# DVR8412.net
KiCad netlist of a schematic drawn in Altium Designer
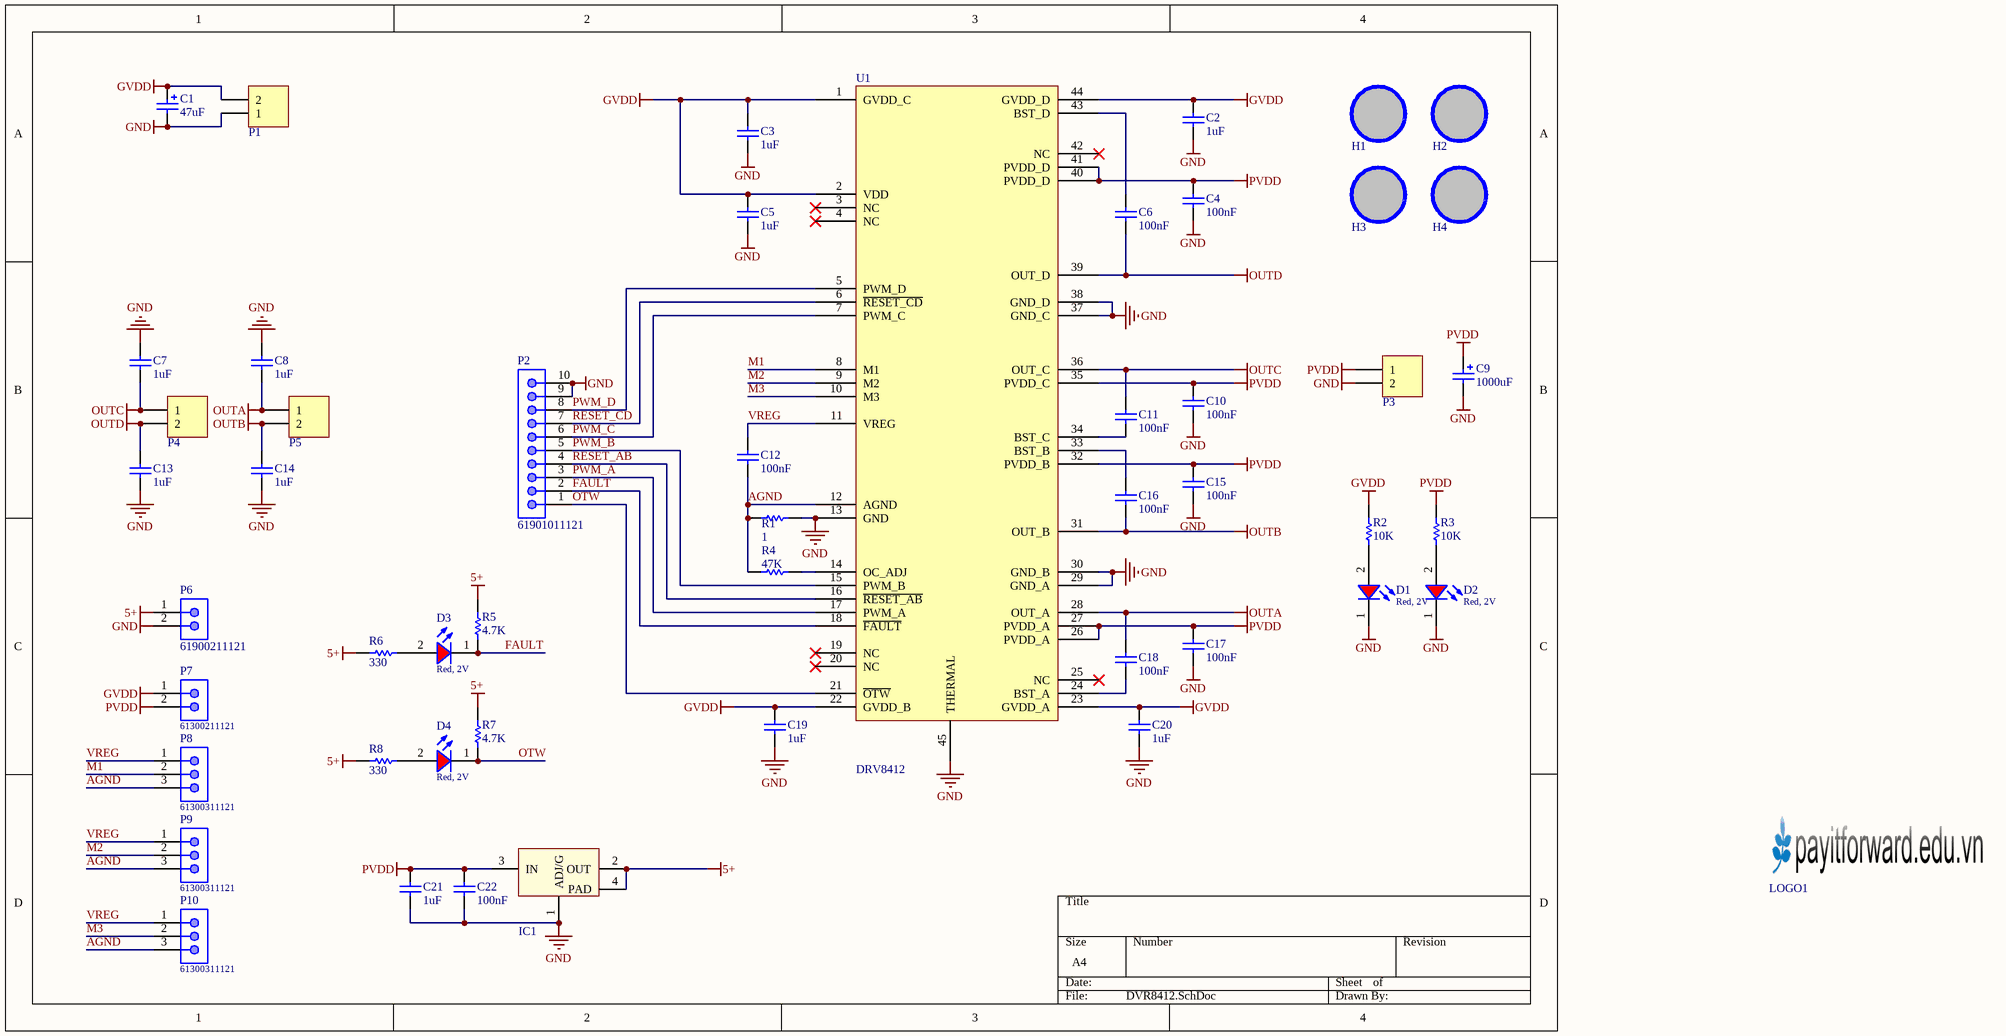
[diagram p0: DVR8412.SchDoc]

(export (version "E")
  (design (tool "Eeschema 10.0.6"))
  (components
    (comp (ref "C1")
      (value "47uF")
      (footprint "CAP ALU SIZE D")
      (description "Polarized Capacitor (Radial)")
      (fields (field (name "Comment") "Cap Pol SMD"))
      (libsource (lib "PIF_Library") (part "Cap Pol SMD"))
    )
    (comp (ref "C2")
      (value "1uF")
      (footprint "CAP-SM-0603")
      (description "Capacitor")
      (fields (field (name "Comment") "Cap Non-Pol SMD"))
      (libsource (lib "PIF_Library") (part "Cap Non-Pol SMD"))
    )
    (comp (ref "C3")
      (value "1uF")
      (footprint "CAP-SM-0603")
      (description "Capacitor")
      (fields (field (name "Comment") "Cap Non-Pol SMD"))
      (libsource (lib "PIF_Library") (part "Cap Non-Pol SMD"))
    )
    (comp (ref "C4")
      (value "100nF")
      (footprint "CAP-SM-0603")
      (description "Capacitor")
      (fields (field (name "Comment") "Cap Non-Pol SMD"))
      (libsource (lib "PIF_Library") (part "Cap Non-Pol SMD"))
    )
    (comp (ref "C5")
      (value "1uF")
      (footprint "CAP-SM-0603")
      (description "Capacitor")
      (fields (field (name "Comment") "Cap Non-Pol SMD"))
      (libsource (lib "PIF_Library") (part "Cap Non-Pol SMD"))
    )
    (comp (ref "C6")
      (value "100nF")
      (footprint "CAP-SM-0603")
      (description "Capacitor")
      (fields (field (name "Comment") "Cap Non-Pol SMD"))
      (libsource (lib "PIF_Library") (part "Cap Non-Pol SMD"))
    )
    (comp (ref "C7")
      (value "1uF")
      (footprint "CAP-SM-0805")
      (description "Capacitor")
      (fields (field (name "Comment") "Cap Non-Pol SMD"))
      (libsource (lib "PIF_Library") (part "Cap Non-Pol SMD"))
    )
    (comp (ref "C8")
      (value "1uF")
      (footprint "CAP-SM-0805")
      (description "Capacitor")
      (fields (field (name "Comment") "Cap Non-Pol SMD"))
      (libsource (lib "PIF_Library") (part "Cap Non-Pol SMD"))
    )
    (comp (ref "C9")
      (value "1000uF")
      (footprint "CP2/5")
      (description "Polarized Capacitor (Radial)")
      (fields (field (name "Comment") "Cap Pol"))
      (libsource (lib "PIF_Library") (part "Cap Pol"))
    )
    (comp (ref "C10")
      (value "100nF")
      (footprint "CAP-SM-0603")
      (description "Capacitor")
      (fields (field (name "Comment") "Cap Non-Pol SMD"))
      (libsource (lib "PIF_Library") (part "Cap Non-Pol SMD"))
    )
    (comp (ref "C11")
      (value "100nF")
      (footprint "CAP-SM-0603")
      (description "Capacitor")
      (fields (field (name "Comment") "Cap Non-Pol SMD"))
      (libsource (lib "PIF_Library") (part "Cap Non-Pol SMD"))
    )
    (comp (ref "C12")
      (value "100nF")
      (footprint "CAP-SM-0603")
      (description "Capacitor")
      (fields (field (name "Comment") "Cap Non-Pol SMD"))
      (libsource (lib "PIF_Library") (part "Cap Non-Pol SMD"))
    )
    (comp (ref "C13")
      (value "1uF")
      (footprint "CAP-SM-0805")
      (description "Capacitor")
      (fields (field (name "Comment") "Cap Non-Pol SMD"))
      (libsource (lib "PIF_Library") (part "Cap Non-Pol SMD"))
    )
    (comp (ref "C14")
      (value "1uF")
      (footprint "CAP-SM-0805")
      (description "Capacitor")
      (fields (field (name "Comment") "Cap Non-Pol SMD"))
      (libsource (lib "PIF_Library") (part "Cap Non-Pol SMD"))
    )
    (comp (ref "C15")
      (value "100nF")
      (footprint "CAP-SM-0603")
      (description "Capacitor")
      (fields (field (name "Comment") "Cap Non-Pol SMD"))
      (libsource (lib "PIF_Library") (part "Cap Non-Pol SMD"))
    )
    (comp (ref "C16")
      (value "100nF")
      (footprint "CAP-SM-0603")
      (description "Capacitor")
      (fields (field (name "Comment") "Cap Non-Pol SMD"))
      (libsource (lib "PIF_Library") (part "Cap Non-Pol SMD"))
    )
    (comp (ref "C17")
      (value "100nF")
      (footprint "CAP-SM-0603")
      (description "Capacitor")
      (fields (field (name "Comment") "Cap Non-Pol SMD"))
      (libsource (lib "PIF_Library") (part "Cap Non-Pol SMD"))
    )
    (comp (ref "C18")
      (value "100nF")
      (footprint "CAP-SM-0603")
      (description "Capacitor")
      (fields (field (name "Comment") "Cap Non-Pol SMD"))
      (libsource (lib "PIF_Library") (part "Cap Non-Pol SMD"))
    )
    (comp (ref "C19")
      (value "1uF")
      (footprint "CAP-SM-0603")
      (description "Capacitor")
      (fields (field (name "Comment") "Cap Non-Pol SMD"))
      (libsource (lib "PIF_Library") (part "Cap Non-Pol SMD"))
    )
    (comp (ref "C20")
      (value "1uF")
      (footprint "CAP-SM-0603")
      (description "Capacitor")
      (fields (field (name "Comment") "Cap Non-Pol SMD"))
      (libsource (lib "PIF_Library") (part "Cap Non-Pol SMD"))
    )
    (comp (ref "C21")
      (value "1uF")
      (footprint "CAP-SM-0603")
      (description "Capacitor")
      (fields (field (name "Comment") "Cap Non-Pol SMD"))
      (libsource (lib "PIF_Library") (part "Cap Non-Pol SMD"))
    )
    (comp (ref "C22")
      (value "100nF")
      (footprint "CAP-SM-0603")
      (description "Capacitor")
      (fields (field (name "Comment") "Cap Non-Pol SMD"))
      (libsource (lib "PIF_Library") (part "Cap Non-Pol SMD"))
    )
    (comp (ref "D1")
      (value "Red, 2V")
      (footprint "WL-SMCW_0603_H=0.7mm")
      (description "WL-SMCW SMT Mono-color Chip LED Waterclear, size 0603, Red, 2V, 140deg")
      (fields (field (name "PART NUMBER") "150060RS75000") (field (name "PUBLISHER") "Wurth Elektronik"))
      (libsource (lib "Altium_WL-SMCW (rev20a)") (part "150060RS75000"))
    )
    (comp (ref "D2")
      (value "Red, 2V")
      (footprint "WL-SMCW_0603_H=0.7mm")
      (description "WL-SMCW SMT Mono-color Chip LED Waterclear, size 0603, Red, 2V, 140deg")
      (fields (field (name "PART NUMBER") "150060RS75000") (field (name "PUBLISHER") "Wurth Elektronik"))
      (libsource (lib "Altium_WL-SMCW (rev20a)") (part "150060RS75000"))
    )
    (comp (ref "D3")
      (value "Red, 2V")
      (footprint "WL-SMCW_0603_H=0.7mm")
      (description "WL-SMCW SMT Mono-color Chip LED Waterclear, size 0603, Red, 2V, 140deg")
      (fields (field (name "PART NUMBER") "150060RS75000") (field (name "PUBLISHER") "Wurth Elektronik"))
      (libsource (lib "Altium_WL-SMCW (rev20a)") (part "150060RS75000"))
    )
    (comp (ref "D4")
      (value "Red, 2V")
      (footprint "WL-SMCW_0603_H=0.7mm")
      (description "WL-SMCW SMT Mono-color Chip LED Waterclear, size 0603, Red, 2V, 140deg")
      (fields (field (name "PART NUMBER") "150060RS75000") (field (name "PUBLISHER") "Wurth Elektronik"))
      (libsource (lib "Altium_WL-SMCW (rev20a)") (part "150060RS75000"))
    )
    (comp (ref "H1")
      (value "Hole")
      (footprint "LO KHOAN 3MM")
      (description "Hole 3mm")
      (libsource (lib "PIF_Library") (part "Hole"))
    )
    (comp (ref "H2")
      (value "Hole")
      (footprint "LO KHOAN 3MM")
      (description "Hole 3mm")
      (libsource (lib "PIF_Library") (part "Hole"))
    )
    (comp (ref "H3")
      (value "Hole")
      (footprint "LO KHOAN 3MM")
      (description "Hole 3mm")
      (libsource (lib "PIF_Library") (part "Hole"))
    )
    (comp (ref "H4")
      (value "Hole")
      (footprint "LO KHOAN 3MM")
      (description "Hole 3mm")
      (libsource (lib "PIF_Library") (part "Hole"))
    )
    (comp (ref "IC1")
      (value "LM1117")
      (footprint "SOT223-4N")
      (description "Available in 1.8V, 2.5V, 2.85V, 3.3V, 5V, and  Adjustable Versions")
      (libsource (lib "PIF_Library") (part "LM1117"))
    )
    (comp (ref "LOGO1")
      (value "LOGO PIF")
      (footprint "PIF LOGO SMALL TOP")
      (libsource (lib "PIF_Library") (part "LOGO PIF"))
    )
    (comp (ref "P1")
      (value "Domino 2")
      (footprint "DOMINO 2- 5mm")
      (description "Domino, 2-Pin")
      (fields (field (name "PUBLISHER") "Altium Limited"))
      (libsource (lib "") (part "Domino 2_1"))
    )
    (comp (ref "P2")
      (value "61901011121")
      (footprint "61901011121")
      (description "WR-WTB THT Male Vertical Locking Header, pitch 2.54mm, 10p")
      (fields (field (name "PUBLISHER") "Wurth Elektronik"))
      (libsource (lib "653008114822_Altium_WR-WTB_rev20a") (part "61901011121"))
    )
    (comp (ref "P3")
      (value "Domino 2")
      (footprint "DOMINO 2- 5mm")
      (description "Domino, 2-Pin")
      (fields (field (name "PUBLISHER") "Altium Limited"))
      (libsource (lib "PIF_Library") (part "Domino 2"))
    )
    (comp (ref "P4")
      (value "Domino 2")
      (footprint "DOMINO 2- 5mm")
      (description "Domino, 2-Pin")
      (fields (field (name "PUBLISHER") "Altium Limited"))
      (libsource (lib "PIF_Library") (part "Domino 2"))
    )
    (comp (ref "P5")
      (value "Domino 2")
      (footprint "DOMINO 2- 5mm")
      (description "Domino, 2-Pin")
      (fields (field (name "PUBLISHER") "Altium Limited"))
      (libsource (lib "PIF_Library") (part "Domino 2"))
    )
    (comp (ref "P6")
      (value "61900211121")
      (footprint "61900211121")
      (description "WR-WTB THT Male Vertical Locking Header, pitch 2.54mm, 2p")
      (fields (field (name "PUBLISHER") "Wurth Elektronik"))
      (libsource (lib "653008114822_Altium_WR-WTB_rev20a") (part "61900211121"))
    )
    (comp (ref "P7")
      (value "61300211121")
      (footprint "61300211121")
      (description "WR-PHD Pin Header, THT, pitch 2.54mm, Single Row, Vertical, 2p")
      (fields (field (name "MANUFACTURER") "Wurth Elektronik"))
      (libsource (lib "Altium_WR-PHD (rev20a)") (part "61300211121"))
    )
    (comp (ref "P8")
      (value "61300311121")
      (footprint "61300311121")
      (description "WR-PHD Pin Header, THT, pitch 2.54mm, Single Row, Vertical, 3p")
      (fields (field (name "MANUFACTURER") "Wurth Elektronik"))
      (libsource (lib "Altium_WR-PHD (rev20a)") (part "61300311121"))
    )
    (comp (ref "P9")
      (value "61300311121")
      (footprint "61300311121")
      (description "WR-PHD Pin Header, THT, pitch 2.54mm, Single Row, Vertical, 3p")
      (fields (field (name "MANUFACTURER") "Wurth Elektronik"))
      (libsource (lib "Altium_WR-PHD (rev20a)") (part "61300311121"))
    )
    (comp (ref "P10")
      (value "61300311121")
      (footprint "61300311121")
      (description "WR-PHD Pin Header, THT, pitch 2.54mm, Single Row, Vertical, 3p")
      (fields (field (name "MANUFACTURER") "Wurth Elektronik"))
      (libsource (lib "Altium_WR-PHD (rev20a)") (part "61300311121"))
    )
    (comp (ref "R1")
      (value "1")
      (footprint "RES-SM-0603")
      (description "Resistor")
      (fields (field (name "Comment") "RESISTOR SMD"))
      (libsource (lib "PIF_Library") (part "RESISTOR SMD"))
    )
    (comp (ref "R2")
      (value "10K")
      (footprint "RES-SM-0603")
      (description "Resistor")
      (fields (field (name "Comment") "RESISTOR SMD"))
      (libsource (lib "PIF_Library") (part "RESISTOR SMD"))
    )
    (comp (ref "R3")
      (value "10K")
      (footprint "RES-SM-0603")
      (description "Resistor")
      (fields (field (name "Comment") "RESISTOR SMD"))
      (libsource (lib "PIF_Library") (part "RESISTOR SMD"))
    )
    (comp (ref "R4")
      (value "47K")
      (footprint "RES-SM-0603")
      (description "Resistor")
      (fields (field (name "Comment") "RESISTOR SMD"))
      (libsource (lib "PIF_Library") (part "RESISTOR SMD"))
    )
    (comp (ref "R5")
      (value "4.7K")
      (footprint "RES-SM-0603")
      (description "Resistor")
      (fields (field (name "Comment") "RESISTOR SMD"))
      (libsource (lib "PIF_Library") (part "RESISTOR SMD"))
    )
    (comp (ref "R6")
      (value "330")
      (footprint "RES-SM-0603")
      (description "Resistor")
      (fields (field (name "Comment") "RESISTOR SMD"))
      (libsource (lib "PIF_Library") (part "RESISTOR SMD"))
    )
    (comp (ref "R7")
      (value "4.7K")
      (footprint "RES-SM-0603")
      (description "Resistor")
      (fields (field (name "Comment") "RESISTOR SMD"))
      (libsource (lib "PIF_Library") (part "RESISTOR SMD"))
    )
    (comp (ref "R8")
      (value "330")
      (footprint "RES-SM-0603")
      (description "Resistor")
      (fields (field (name "Comment") "RESISTOR SMD"))
      (libsource (lib "PIF_Library") (part "RESISTOR SMD"))
    )
    (comp (ref "U1")
      (value "DRV8412")
      (footprint "TSOP64P810X150_HS-45N")
      (fields (field (name "MANUFACTURER") "Texas Instruments"))
      (libsource (lib "MiclsLib") (part "DRV8412"))
    )
  )
  (nets
    (net (code "1") (name "/AGND") (class "Default")
      (node (ref "C12") (pin "1") (pinfunction "1_1") (pintype "passive"))
      (node (ref "P10") (pin "3") (pinfunction "3_3") (pintype "passive"))
      (node (ref "P8") (pin "3") (pinfunction "3_3") (pintype "passive"))
      (node (ref "P9") (pin "3") (pinfunction "3_3") (pintype "passive"))
      (node (ref "R1") (pin "1") (pinfunction "1_1") (pintype "passive"))
      (node (ref "R4") (pin "1") (pinfunction "1_1") (pintype "passive"))
      (node (ref "U1") (pin "12") (pinfunction "AGND_12") (pintype "passive"))
    )
    (net (code "2") (name "/FAULT") (class "Default")
      (node (ref "D3") (pin "1") (pinfunction "K_1") (pintype "passive"))
      (node (ref "P2") (pin "2") (pinfunction "2_2") (pintype "passive"))
      (node (ref "R5") (pin "1") (pinfunction "1_1") (pintype "passive"))
      (node (ref "U1") (pin "18") (pinfunction "~{FAULT}_18") (pintype "passive"))
    )
    (net (code "3") (name "/M1") (class "Default")
      (node (ref "P8") (pin "2") (pinfunction "2_2") (pintype "passive"))
      (node (ref "U1") (pin "8") (pinfunction "M1_8") (pintype "passive"))
    )
    (net (code "4") (name "/M2") (class "Default")
      (node (ref "P9") (pin "2") (pinfunction "2_2") (pintype "passive"))
      (node (ref "U1") (pin "9") (pinfunction "M2_9") (pintype "passive"))
    )
    (net (code "5") (name "/M3") (class "Default")
      (node (ref "P10") (pin "2") (pinfunction "2_2") (pintype "passive"))
      (node (ref "U1") (pin "10") (pinfunction "M3_10") (pintype "passive"))
    )
    (net (code "6") (name "/OTW") (class "Default")
      (node (ref "D4") (pin "1") (pinfunction "K_1") (pintype "passive"))
      (node (ref "P2") (pin "1") (pinfunction "1_1") (pintype "passive"))
      (node (ref "R7") (pin "1") (pinfunction "1_1") (pintype "passive"))
      (node (ref "U1") (pin "21") (pinfunction "~{OTW}_21") (pintype "passive"))
    )
    (net (code "7") (name "/PWM_A") (class "Default")
      (node (ref "P2") (pin "3") (pinfunction "3_3") (pintype "passive"))
      (node (ref "U1") (pin "17") (pinfunction "PWM_A_17") (pintype "passive"))
    )
    (net (code "8") (name "/PWM_B") (class "Default")
      (node (ref "P2") (pin "5") (pinfunction "5_5") (pintype "passive"))
      (node (ref "U1") (pin "15") (pinfunction "PWM_B_15") (pintype "passive"))
    )
    (net (code "9") (name "/PWM_C") (class "Default")
      (node (ref "P2") (pin "6") (pinfunction "6_6") (pintype "passive"))
      (node (ref "U1") (pin "7") (pinfunction "PWM_C_7") (pintype "passive"))
    )
    (net (code "10") (name "/PWM_D") (class "Default")
      (node (ref "P2") (pin "8") (pinfunction "8_8") (pintype "passive"))
      (node (ref "U1") (pin "5") (pinfunction "PWM_D_5") (pintype "passive"))
    )
    (net (code "11") (name "/RESET_AB") (class "Default")
      (node (ref "P2") (pin "4") (pinfunction "4_4") (pintype "passive"))
      (node (ref "U1") (pin "16") (pinfunction "~{RESET_AB}_16") (pintype "passive"))
    )
    (net (code "12") (name "/RESET_CD") (class "Default")
      (node (ref "P2") (pin "7") (pinfunction "7_7") (pintype "passive"))
      (node (ref "U1") (pin "6") (pinfunction "~{RESET_CD}_6") (pintype "passive"))
    )
    (net (code "13") (name "/VREG") (class "Default")
      (node (ref "C12") (pin "2") (pinfunction "2_2") (pintype "passive"))
      (node (ref "P10") (pin "1") (pinfunction "1_1") (pintype "passive"))
      (node (ref "P8") (pin "1") (pinfunction "1_1") (pintype "passive"))
      (node (ref "P9") (pin "1") (pinfunction "1_1") (pintype "passive"))
      (node (ref "U1") (pin "11") (pinfunction "VREG_11") (pintype "passive"))
    )
    (net (code "14") (name "5+") (class "Default")
      (node (ref "IC1") (pin "2") (pinfunction "OUT_2") (pintype "passive"))
      (node (ref "IC1") (pin "4") (pinfunction "PAD_4") (pintype "passive"))
      (node (ref "P6") (pin "1") (pinfunction "1_1") (pintype "passive"))
      (node (ref "R5") (pin "2") (pinfunction "2_2") (pintype "passive"))
      (node (ref "R6") (pin "2") (pinfunction "2_2") (pintype "passive"))
      (node (ref "R7") (pin "2") (pinfunction "2_2") (pintype "passive"))
      (node (ref "R8") (pin "2") (pinfunction "2_2") (pintype "passive"))
    )
    (net (code "15") (name "GND") (class "Default")
      (node (ref "C1") (pin "2") (pinfunction "2_2") (pintype "passive"))
      (node (ref "C10") (pin "1") (pinfunction "1_1") (pintype "passive"))
      (node (ref "C13") (pin "1") (pinfunction "1_1") (pintype "passive"))
      (node (ref "C14") (pin "1") (pinfunction "1_1") (pintype "passive"))
      (node (ref "C15") (pin "1") (pinfunction "1_1") (pintype "passive"))
      (node (ref "C17") (pin "1") (pinfunction "1_1") (pintype "passive"))
      (node (ref "C19") (pin "1") (pinfunction "1_1") (pintype "passive"))
      (node (ref "C2") (pin "1") (pinfunction "1_1") (pintype "passive"))
      (node (ref "C20") (pin "1") (pinfunction "1_1") (pintype "passive"))
      (node (ref "C21") (pin "1") (pinfunction "1_1") (pintype "passive"))
      (node (ref "C22") (pin "1") (pinfunction "1_1") (pintype "passive"))
      (node (ref "C3") (pin "1") (pinfunction "1_1") (pintype "passive"))
      (node (ref "C4") (pin "1") (pinfunction "1_1") (pintype "passive"))
      (node (ref "C5") (pin "1") (pinfunction "1_1") (pintype "passive"))
      (node (ref "C7") (pin "2") (pinfunction "2_2") (pintype "passive"))
      (node (ref "C8") (pin "2") (pinfunction "2_2") (pintype "passive"))
      (node (ref "C9") (pin "2") (pinfunction "2_2") (pintype "passive"))
      (node (ref "D1") (pin "1") (pinfunction "K_1") (pintype "passive"))
      (node (ref "D2") (pin "1") (pinfunction "K_1") (pintype "passive"))
      (node (ref "IC1") (pin "1") (pinfunction "ADJ/G_1") (pintype "passive"))
      (node (ref "P1") (pin "1") (pinfunction "1_1") (pintype "passive"))
      (node (ref "P2") (pin "10") (pinfunction "10_10") (pintype "passive"))
      (node (ref "P2") (pin "9") (pinfunction "9_9") (pintype "passive"))
      (node (ref "P3") (pin "2") (pinfunction "2_2") (pintype "passive"))
      (node (ref "P6") (pin "2") (pinfunction "2_2") (pintype "passive"))
      (node (ref "R1") (pin "2") (pinfunction "2_2") (pintype "passive"))
      (node (ref "U1") (pin "13") (pinfunction "GND_13") (pintype "passive"))
      (node (ref "U1") (pin "29") (pinfunction "GND_A_29") (pintype "passive"))
      (node (ref "U1") (pin "30") (pinfunction "GND_B_30") (pintype "passive"))
      (node (ref "U1") (pin "37") (pinfunction "GND_C_37") (pintype "passive"))
      (node (ref "U1") (pin "38") (pinfunction "GND_D_38") (pintype "passive"))
      (node (ref "U1") (pin "45") (pinfunction "THERMAL_45") (pintype "passive"))
    )
    (net (code "16") (name "GVDD") (class "Default")
      (node (ref "C1") (pin "1") (pinfunction "1_1") (pintype "passive"))
      (node (ref "C19") (pin "2") (pinfunction "2_2") (pintype "passive"))
      (node (ref "C2") (pin "2") (pinfunction "2_2") (pintype "passive"))
      (node (ref "C20") (pin "2") (pinfunction "2_2") (pintype "passive"))
      (node (ref "C3") (pin "2") (pinfunction "2_2") (pintype "passive"))
      (node (ref "C5") (pin "2") (pinfunction "2_2") (pintype "passive"))
      (node (ref "P1") (pin "2") (pinfunction "2_2") (pintype "passive"))
      (node (ref "P7") (pin "1") (pinfunction "1_1") (pintype "passive"))
      (node (ref "R2") (pin "1") (pinfunction "1_1") (pintype "passive"))
      (node (ref "U1") (pin "1") (pinfunction "GVDD_C_1") (pintype "passive"))
      (node (ref "U1") (pin "2") (pinfunction "VDD_2") (pintype "passive"))
      (node (ref "U1") (pin "22") (pinfunction "GVDD_B_22") (pintype "passive"))
      (node (ref "U1") (pin "23") (pinfunction "GVDD_A_23") (pintype "passive"))
      (node (ref "U1") (pin "44") (pinfunction "GVDD_D_44") (pintype "passive"))
    )
    (net (code "17") (name "Net-(D1-A)") (class "Default")
      (node (ref "D1") (pin "2") (pinfunction "A_2") (pintype "passive"))
      (node (ref "R2") (pin "2") (pinfunction "2_2") (pintype "passive"))
    )
    (net (code "18") (name "Net-(D2-A)") (class "Default")
      (node (ref "D2") (pin "2") (pinfunction "A_2") (pintype "passive"))
      (node (ref "R3") (pin "2") (pinfunction "2_2") (pintype "passive"))
    )
    (net (code "19") (name "Net-(D3-A)") (class "Default")
      (node (ref "D3") (pin "2") (pinfunction "A_2") (pintype "passive"))
      (node (ref "R6") (pin "1") (pinfunction "1_1") (pintype "passive"))
    )
    (net (code "20") (name "Net-(D4-A)") (class "Default")
      (node (ref "D4") (pin "2") (pinfunction "A_2") (pintype "passive"))
      (node (ref "R8") (pin "1") (pinfunction "1_1") (pintype "passive"))
    )
    (net (code "21") (name "Net-(U1-BST_A)") (class "Default")
      (node (ref "C18") (pin "1") (pinfunction "1_1") (pintype "passive"))
      (node (ref "U1") (pin "24") (pinfunction "BST_A_24") (pintype "passive"))
    )
    (net (code "22") (name "Net-(U1-BST_B)") (class "Default")
      (node (ref "C16") (pin "2") (pinfunction "2_2") (pintype "passive"))
      (node (ref "U1") (pin "33") (pinfunction "BST_B_33") (pintype "passive"))
    )
    (net (code "23") (name "Net-(U1-BST_C)") (class "Default")
      (node (ref "C11") (pin "1") (pinfunction "1_1") (pintype "passive"))
      (node (ref "U1") (pin "34") (pinfunction "BST_C_34") (pintype "passive"))
    )
    (net (code "24") (name "Net-(U1-BST_D)") (class "Default")
      (node (ref "C6") (pin "2") (pinfunction "2_2") (pintype "passive"))
      (node (ref "U1") (pin "43") (pinfunction "BST_D_43") (pintype "passive"))
    )
    (net (code "25") (name "Net-(U1-OC_ADJ)") (class "Default")
      (node (ref "R4") (pin "2") (pinfunction "2_2") (pintype "passive"))
      (node (ref "U1") (pin "14") (pinfunction "OC_ADJ_14") (pintype "passive"))
    )
    (net (code "26") (name "OUTA") (class "Default")
      (node (ref "C18") (pin "2") (pinfunction "2_2") (pintype "passive"))
      (node (ref "C8") (pin "1") (pinfunction "1_1") (pintype "passive"))
      (node (ref "P5") (pin "1") (pinfunction "1_1") (pintype "passive"))
      (node (ref "U1") (pin "28") (pinfunction "OUT_A_28") (pintype "passive"))
    )
    (net (code "27") (name "OUTB") (class "Default")
      (node (ref "C14") (pin "2") (pinfunction "2_2") (pintype "passive"))
      (node (ref "C16") (pin "1") (pinfunction "1_1") (pintype "passive"))
      (node (ref "P5") (pin "2") (pinfunction "2_2") (pintype "passive"))
      (node (ref "U1") (pin "31") (pinfunction "OUT_B_31") (pintype "passive"))
    )
    (net (code "28") (name "OUTC") (class "Default")
      (node (ref "C11") (pin "2") (pinfunction "2_2") (pintype "passive"))
      (node (ref "C7") (pin "1") (pinfunction "1_1") (pintype "passive"))
      (node (ref "P4") (pin "1") (pinfunction "1_1") (pintype "passive"))
      (node (ref "U1") (pin "36") (pinfunction "OUT_C_36") (pintype "passive"))
    )
    (net (code "29") (name "OUTD") (class "Default")
      (node (ref "C13") (pin "2") (pinfunction "2_2") (pintype "passive"))
      (node (ref "C6") (pin "1") (pinfunction "1_1") (pintype "passive"))
      (node (ref "P4") (pin "2") (pinfunction "2_2") (pintype "passive"))
      (node (ref "U1") (pin "39") (pinfunction "OUT_D_39") (pintype "passive"))
    )
    (net (code "30") (name "PVDD") (class "Default")
      (node (ref "C10") (pin "2") (pinfunction "2_2") (pintype "passive"))
      (node (ref "C15") (pin "2") (pinfunction "2_2") (pintype "passive"))
      (node (ref "C17") (pin "2") (pinfunction "2_2") (pintype "passive"))
      (node (ref "C21") (pin "2") (pinfunction "2_2") (pintype "passive"))
      (node (ref "C22") (pin "2") (pinfunction "2_2") (pintype "passive"))
      (node (ref "C4") (pin "2") (pinfunction "2_2") (pintype "passive"))
      (node (ref "C9") (pin "1") (pinfunction "1_1") (pintype "passive"))
      (node (ref "IC1") (pin "3") (pinfunction "IN_3") (pintype "passive"))
      (node (ref "P3") (pin "1") (pinfunction "1_1") (pintype "passive"))
      (node (ref "P7") (pin "2") (pinfunction "2_2") (pintype "passive"))
      (node (ref "R3") (pin "1") (pinfunction "1_1") (pintype "passive"))
      (node (ref "U1") (pin "26") (pinfunction "PVDD_A_26") (pintype "passive"))
      (node (ref "U1") (pin "27") (pinfunction "PVDD_A_27") (pintype "passive"))
      (node (ref "U1") (pin "32") (pinfunction "PVDD_B_32") (pintype "passive"))
      (node (ref "U1") (pin "35") (pinfunction "PVDD_C_35") (pintype "passive"))
      (node (ref "U1") (pin "40") (pinfunction "PVDD_D_40") (pintype "passive"))
      (node (ref "U1") (pin "41") (pinfunction "PVDD_D_41") (pintype "passive"))
    )
    (net (code "31") (name "unconnected-(H1-Pad1)") (class "Default")
      (node (ref "H1") (pin "1") (pinfunction "1_1") (pintype "passive"))
    )
    (net (code "32") (name "unconnected-(H2-Pad1)") (class "Default")
      (node (ref "H2") (pin "1") (pinfunction "1_1") (pintype "passive"))
    )
    (net (code "33") (name "unconnected-(H3-Pad1)") (class "Default")
      (node (ref "H3") (pin "1") (pinfunction "1_1") (pintype "passive"))
    )
    (net (code "34") (name "unconnected-(H4-Pad1)") (class "Default")
      (node (ref "H4") (pin "1") (pinfunction "1_1") (pintype "passive"))
    )
    (net (code "35") (name "unconnected-(U1-NC-Pad3)") (class "Default")
      (node (ref "U1") (pin "3") (pinfunction "NC_3") (pintype "passive+no_connect"))
    )
    (net (code "36") (name "unconnected-(U1-NC-Pad4)") (class "Default")
      (node (ref "U1") (pin "4") (pinfunction "NC_4") (pintype "passive+no_connect"))
    )
    (net (code "37") (name "unconnected-(U1-NC-Pad19)") (class "Default")
      (node (ref "U1") (pin "19") (pinfunction "NC_19") (pintype "passive+no_connect"))
    )
    (net (code "38") (name "unconnected-(U1-NC-Pad20)") (class "Default")
      (node (ref "U1") (pin "20") (pinfunction "NC_20") (pintype "passive+no_connect"))
    )
    (net (code "39") (name "unconnected-(U1-NC-Pad25)") (class "Default")
      (node (ref "U1") (pin "25") (pinfunction "NC_25") (pintype "passive+no_connect"))
    )
    (net (code "40") (name "unconnected-(U1-NC-Pad42)") (class "Default")
      (node (ref "U1") (pin "42") (pinfunction "NC_42") (pintype "passive+no_connect"))
    )
  )
)
